# POWER.net
KiCad netlist of a schematic drawn in Altium Designer
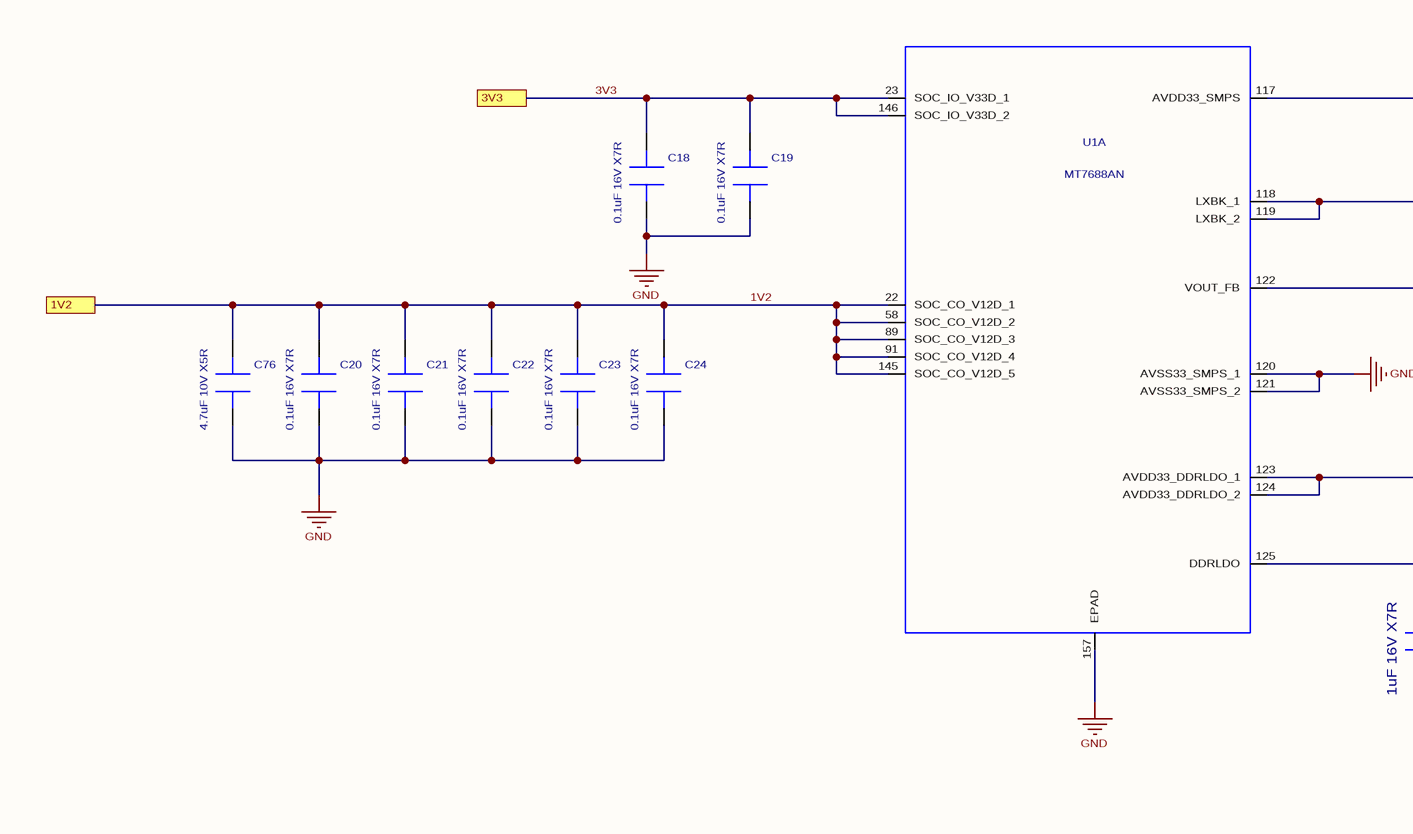
[diagram p0: POWER.SchDoc, left]
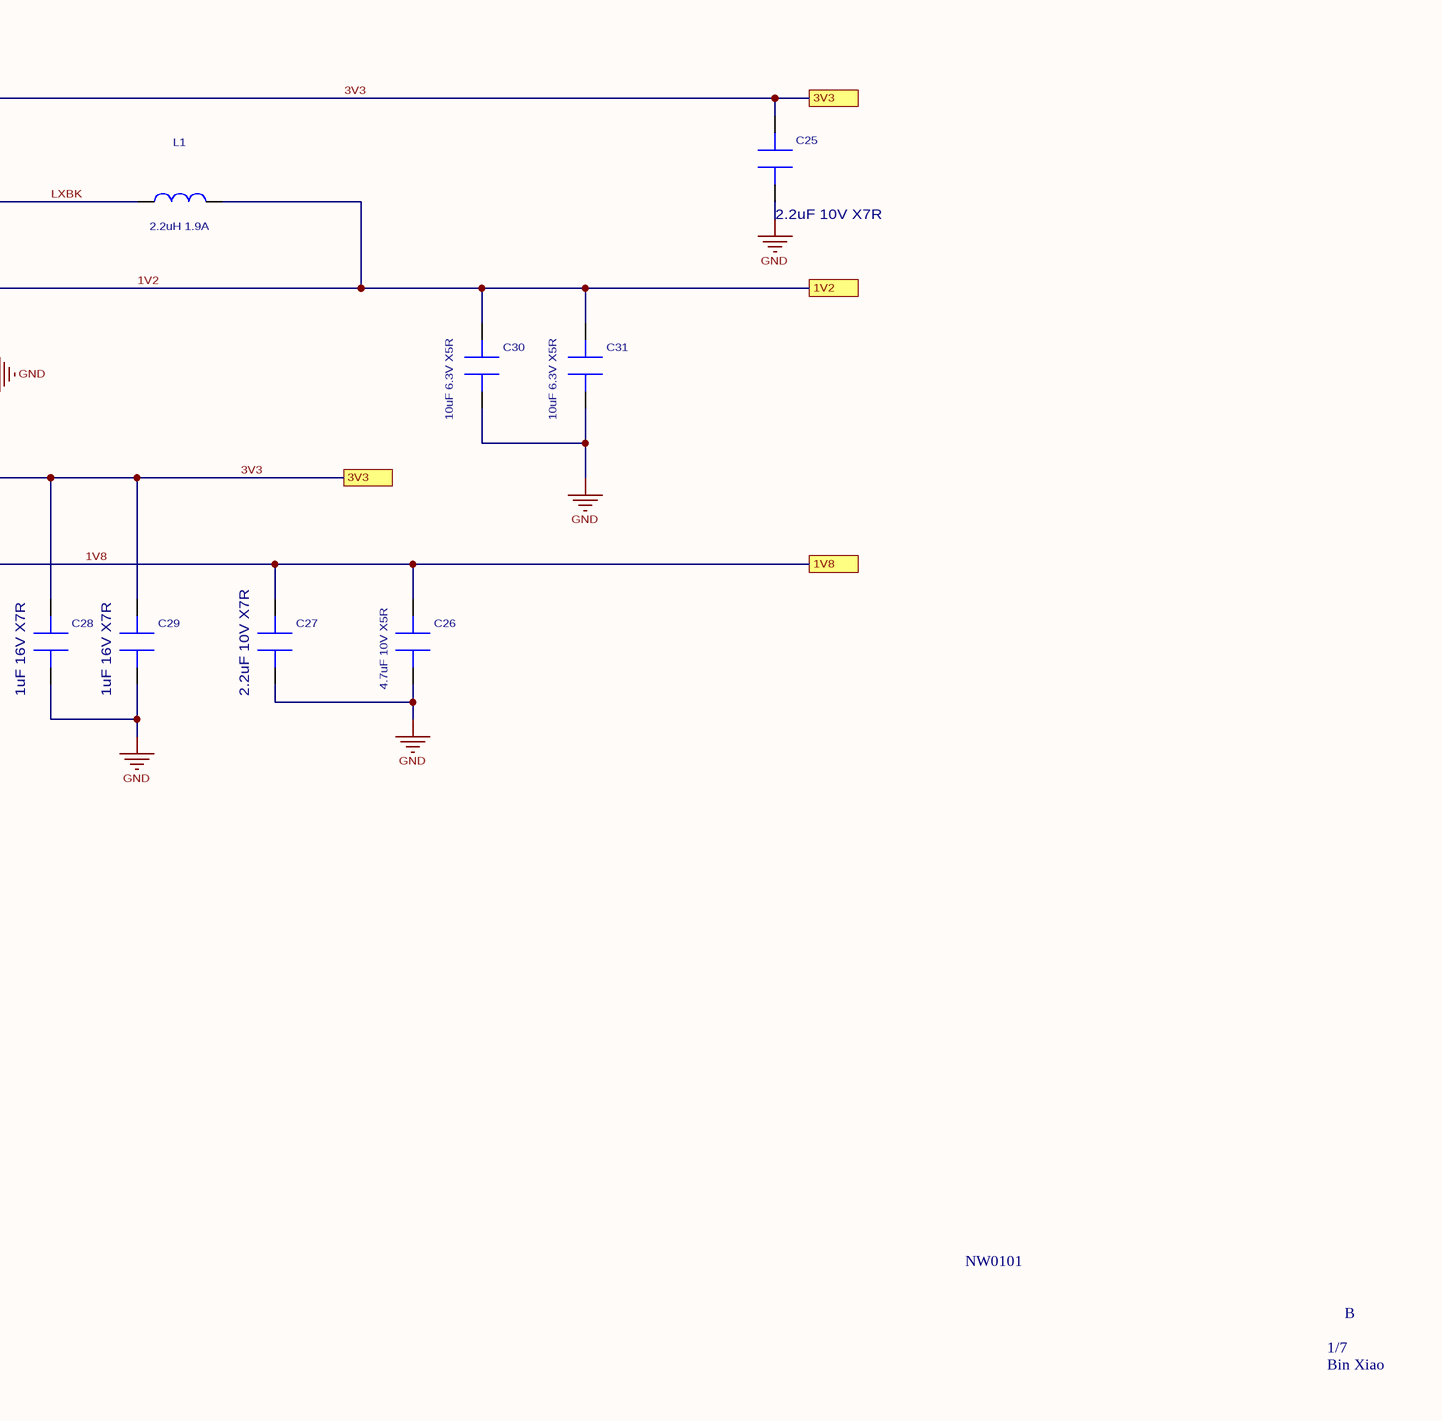
[diagram p1: POWER.SchDoc, right]

(export (version "E")
  (design (tool "Eeschema 10.0.6"))
  (components
    (comp (ref "C18")
      (value "0.1uF 16V X7R")
      (footprint "C0201")
      (description "CAP CER 0.1UF 16V X7R 0201")
      (fields
        (field (name "PART NUMBER") "GRM033Z71C104KE14D")
        (field (name "MANUFACTURER") "Murata Electronics")
      )
      (libsource (lib "NetworkModule") (part "CAP0201-104-16V-X7R"))
    )
    (comp (ref "C19")
      (value "0.1uF 16V X7R")
      (footprint "C0201")
      (description "CAP CER 0.1UF 16V X7R 0201")
      (fields
        (field (name "PART NUMBER") "GRM033Z71C104KE14D")
        (field (name "MANUFACTURER") "Murata Electronics")
      )
      (libsource (lib "NetworkModule") (part "CAP0201-104-16V-X7R"))
    )
    (comp (ref "C20")
      (value "0.1uF 16V X7R")
      (footprint "C0201")
      (description "CAP CER 0.1UF 16V X7R 0201")
      (fields
        (field (name "PART NUMBER") "GRM033Z71C104KE14D")
        (field (name "MANUFACTURER") "Murata Electronics")
      )
      (libsource (lib "NetworkModule") (part "CAP0201-104-16V-X7R"))
    )
    (comp (ref "C21")
      (value "0.1uF 16V X7R")
      (footprint "C0201")
      (description "CAP CER 0.1UF 16V X7R 0201")
      (fields
        (field (name "PART NUMBER") "GRM033Z71C104KE14D")
        (field (name "MANUFACTURER") "Murata Electronics")
      )
      (libsource (lib "NetworkModule") (part "CAP0201-104-16V-X7R"))
    )
    (comp (ref "C22")
      (value "0.1uF 16V X7R")
      (footprint "C0201")
      (description "CAP CER 0.1UF 16V X7R 0201")
      (fields
        (field (name "PART NUMBER") "GRM033Z71C104KE14D")
        (field (name "MANUFACTURER") "Murata Electronics")
      )
      (libsource (lib "NetworkModule") (part "CAP0201-104-16V-X7R"))
    )
    (comp (ref "C23")
      (value "0.1uF 16V X7R")
      (footprint "C0201")
      (description "CAP CER 0.1UF 16V X7R 0201")
      (fields
        (field (name "PART NUMBER") "GRM033Z71C104KE14D")
        (field (name "MANUFACTURER") "Murata Electronics")
      )
      (libsource (lib "NetworkModule") (part "CAP0201-104-16V-X7R"))
    )
    (comp (ref "C24")
      (value "0.1uF 16V X7R")
      (footprint "C0201")
      (description "CAP CER 0.1UF 16V X7R 0201")
      (fields
        (field (name "PART NUMBER") "GRM033Z71C104KE14D")
        (field (name "MANUFACTURER") "Murata Electronics")
      )
      (libsource (lib "NetworkModule") (part "CAP0201-104-16V-X7R"))
    )
    (comp (ref "C25")
      (value "2.2uF 10V X7R")
      (footprint "C0402")
      (description "CAP CER 2.2UF 10V X7R 0402")
      (fields
        (field (name "PART NUMBER") "GRM155Z71A225KE01D")
        (field (name "MANUFACTURER") "Murata Electronics")
      )
      (libsource (lib "NetworkModule") (part "CAP0402-225-6.3V-X7R"))
    )
    (comp (ref "C26")
      (value "4.7uF 10V X5R")
      (footprint "C0402")
      (description "CAP CER 4.7UF 10V X5R 0402")
      (fields
        (field (name "PART NUMBER") "CL05A475MP5NRNC")
        (field (name "MANUFACTURER") "Samsung Electro-Mechanics")
      )
      (libsource (lib "NetworkModule") (part "CAP0402-475-10V-X5R"))
    )
    (comp (ref "C27")
      (value "2.2uF 10V X7R")
      (footprint "C0402")
      (description "CAP CER 2.2UF 10V X7R 0402")
      (fields
        (field (name "PART NUMBER") "GRM155Z71A225KE01D")
        (field (name "MANUFACTURER") "Murata Electronics")
      )
      (libsource (lib "NetworkModule") (part "CAP0402-225-6.3V-X7R"))
    )
    (comp (ref "C28")
      (value "1uF 16V X7R")
      (footprint "C0402")
      (description "CAP CER 1UF 6.3V X7R 0402")
      (fields
        (field (name "PART NUMBER") "GRM155R70J105KA12D")
        (field (name "MANUFACTURER") "Murata Electronics")
      )
      (libsource (lib "NetworkModule") (part "CAP0402-105-6.3V-X7R"))
    )
    (comp (ref "C29")
      (value "1uF 16V X7R")
      (footprint "C0402")
      (description "CAP CER 1UF 6.3V X7R 0402")
      (fields
        (field (name "PART NUMBER") "GRM155R70J105KA12D")
        (field (name "MANUFACTURER") "Murata Electronics")
      )
      (libsource (lib "NetworkModule") (part "CAP0402-105-6.3V-X7R"))
    )
    (comp (ref "C30")
      (value "10uF 6.3V X5R")
      (footprint "C0402")
      (description "CAP CER 10UF 6.3V X5R 0402")
      (fields
        (field (name "PART NUMBER") "GRM155R60J106ME05J")
        (field (name "MANUFACTURER") "Murata Electronics")
      )
      (libsource (lib "NetworkModule") (part "CAP0402-106-6.3V-X5R"))
    )
    (comp (ref "C31")
      (value "10uF 6.3V X5R")
      (footprint "C0402")
      (description "CAP CER 10UF 6.3V X5R 0402")
      (fields
        (field (name "PART NUMBER") "GRM155R60J106ME05J")
        (field (name "MANUFACTURER") "Murata Electronics")
      )
      (libsource (lib "NetworkModule") (part "CAP0402-106-6.3V-X5R"))
    )
    (comp (ref "C76")
      (value "4.7uF 10V X5R")
      (footprint "C0402")
      (description "CAP CER 4.7UF 10V X5R 0402")
      (fields
        (field (name "PART NUMBER") "CL05A475MP5NRNC")
        (field (name "MANUFACTURER") "Samsung Electro-Mechanics")
      )
      (libsource (lib "NetworkModule") (part "CAP0402-475-10V-X5R"))
    )
    (comp (ref "L1")
      (value "2.2uH 1.9A")
      (footprint "L0805")
      (description "POWER CHOKE MOLDED 2.2UH 1.9A")
      (fields
        (field (name "PART NUMBER") "WLPH201610M2R2PP")
        (field (name "MANUFACTURER") "Walsin Technology Corporation")
      )
      (libsource (lib "NetworkModule") (part "IND0805_2.2U_1.9A"))
    )
    (comp (ref "U1")
      (value "MT7688AN")
      (footprint "DR-QFN-128")
      (description "580Mhz 32bits Networking Processor")
      (fields (field (name "MANUFACTURER") "MediaTek Inc"))
      (libsource (lib "*") (part "MT7688AN"))
    )
  )
  (nets
    (net (code "1") (name "/1V2") (class "Default")
      (node (ref "C20") (pin "1") (pinfunction "1_1") (pintype "passive"))
      (node (ref "C21") (pin "1") (pinfunction "1_1") (pintype "passive"))
      (node (ref "C22") (pin "1") (pinfunction "1_1") (pintype "passive"))
      (node (ref "C23") (pin "1") (pinfunction "1_1") (pintype "passive"))
      (node (ref "C24") (pin "1") (pinfunction "1_1") (pintype "passive"))
      (node (ref "C30") (pin "1") (pinfunction "1_1") (pintype "passive"))
      (node (ref "C31") (pin "1") (pinfunction "1_1") (pintype "passive"))
      (node (ref "C76") (pin "1") (pinfunction "1_1") (pintype "passive"))
      (node (ref "L1") (pin "2") (pinfunction "2_2") (pintype "passive"))
      (node (ref "U1") (pin "122") (pinfunction "VOUT_FB_122") (pintype "passive"))
      (node (ref "U1") (pin "145") (pinfunction "SOC_CO_V12D_5_145") (pintype "passive"))
      (node (ref "U1") (pin "22") (pinfunction "SOC_CO_V12D_1_22") (pintype "passive"))
      (node (ref "U1") (pin "58") (pinfunction "SOC_CO_V12D_2_58") (pintype "passive"))
      (node (ref "U1") (pin "89") (pinfunction "SOC_CO_V12D_3_89") (pintype "passive"))
      (node (ref "U1") (pin "91") (pinfunction "SOC_CO_V12D_4_91") (pintype "passive"))
    )
    (net (code "2") (name "/1V8") (class "Default")
      (node (ref "C26") (pin "1") (pinfunction "1_1") (pintype "passive"))
      (node (ref "C27") (pin "1") (pinfunction "1_1") (pintype "passive"))
      (node (ref "U1") (pin "125") (pinfunction "DDRLDO_125") (pintype "passive"))
    )
    (net (code "3") (name "/3V3") (class "Default")
      (node (ref "C18") (pin "1") (pinfunction "1_1") (pintype "passive"))
      (node (ref "C19") (pin "1") (pinfunction "1_1") (pintype "passive"))
      (node (ref "C25") (pin "1") (pinfunction "1_1") (pintype "passive"))
      (node (ref "C28") (pin "1") (pinfunction "1_1") (pintype "passive"))
      (node (ref "C29") (pin "1") (pinfunction "1_1") (pintype "passive"))
      (node (ref "U1") (pin "117") (pinfunction "AVDD33_SMPS_117") (pintype "passive"))
      (node (ref "U1") (pin "123") (pinfunction "AVDD33_DDRLDO_1_123") (pintype "passive"))
      (node (ref "U1") (pin "124") (pinfunction "AVDD33_DDRLDO_2_124") (pintype "passive"))
      (node (ref "U1") (pin "146") (pinfunction "SOC_IO_V33D_2_146") (pintype "passive"))
      (node (ref "U1") (pin "23") (pinfunction "SOC_IO_V33D_1_23") (pintype "passive"))
    )
    (net (code "4") (name "/LXBK") (class "Default")
      (node (ref "L1") (pin "1") (pinfunction "1_1") (pintype "passive"))
      (node (ref "U1") (pin "118") (pinfunction "LXBK_1_118") (pintype "passive"))
      (node (ref "U1") (pin "119") (pinfunction "LXBK_2_119") (pintype "passive"))
    )
    (net (code "5") (name "GND") (class "Default")
      (node (ref "C18") (pin "2") (pinfunction "2_2") (pintype "passive"))
      (node (ref "C19") (pin "2") (pinfunction "2_2") (pintype "passive"))
      (node (ref "C20") (pin "2") (pinfunction "2_2") (pintype "passive"))
      (node (ref "C21") (pin "2") (pinfunction "2_2") (pintype "passive"))
      (node (ref "C22") (pin "2") (pinfunction "2_2") (pintype "passive"))
      (node (ref "C23") (pin "2") (pinfunction "2_2") (pintype "passive"))
      (node (ref "C24") (pin "2") (pinfunction "2_2") (pintype "passive"))
      (node (ref "C25") (pin "2") (pinfunction "2_2") (pintype "passive"))
      (node (ref "C26") (pin "2") (pinfunction "2_2") (pintype "passive"))
      (node (ref "C27") (pin "2") (pinfunction "2_2") (pintype "passive"))
      (node (ref "C28") (pin "2") (pinfunction "2_2") (pintype "passive"))
      (node (ref "C29") (pin "2") (pinfunction "2_2") (pintype "passive"))
      (node (ref "C30") (pin "2") (pinfunction "2_2") (pintype "passive"))
      (node (ref "C31") (pin "2") (pinfunction "2_2") (pintype "passive"))
      (node (ref "C76") (pin "2") (pinfunction "2_2") (pintype "passive"))
      (node (ref "U1") (pin "120") (pinfunction "AVSS33_SMPS_1_120") (pintype "passive"))
      (node (ref "U1") (pin "121") (pinfunction "AVSS33_SMPS_2_121") (pintype "passive"))
      (node (ref "U1") (pin "157") (pinfunction "EPAD_157") (pintype "passive"))
    )
  )
)
